# 3_classyTKL_EC_mcu.net
KiCad netlist of a schematic drawn in Altium Designer
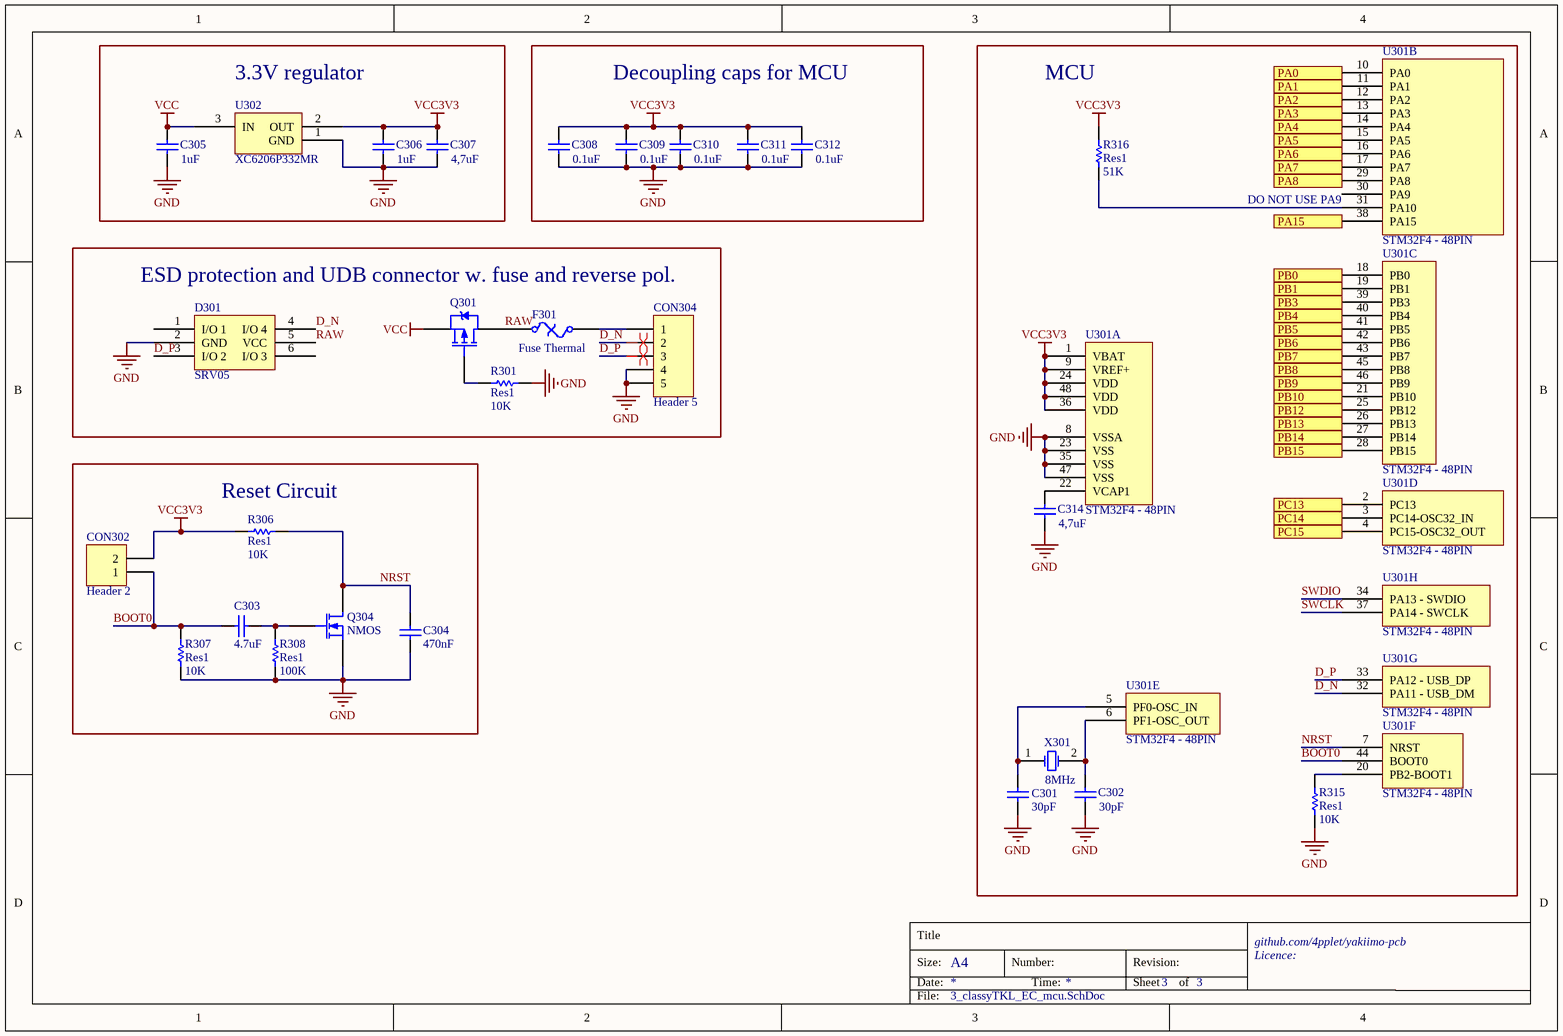
[diagram p0: 3_classyTKL_EC_mcu.SchDoc]

(export (version "E")
  (design (tool "Eeschema 10.0.6"))
  (components
    (comp (ref "C301")
      (value "30pF")
      (footprint "C0603[1608]")
      (description "Capacitor")
      (fields (field (name "LCSC PART #") "C22397") (field (name "MRF.PART") "CL10C300JB8NNNC"))
      (libsource (lib "Miscellaneous Devices") (part "Cap"))
    )
    (comp (ref "C302")
      (value "30pF")
      (footprint "C0603[1608]")
      (description "Capacitor")
      (fields (field (name "LCSC PART #") "C22397") (field (name "MRF.PART") "CL10C300JB8NNNC"))
      (libsource (lib "Miscellaneous Devices") (part "Cap"))
    )
    (comp (ref "C303")
      (value "4.7uF")
      (footprint "C0603[1608]")
      (description "Capacitor")
      (fields (field (name "LCSC PART #") "C19666") (field (name "MRF.PART") "CL10A475KO8NNNC"))
      (libsource (lib "Miscellaneous Devices") (part "Cap"))
    )
    (comp (ref "C304")
      (value "470nF")
      (footprint "C0603[1608]")
      (description "Capacitor")
      (fields (field (name "LCSC PART #") "C14663") (field (name "MRF.PART") "CC0603KRX7R9BB104"))
      (libsource (lib "Miscellaneous Devices") (part "Cap"))
    )
    (comp (ref "C305")
      (value "1uF")
      (footprint "C0603[1608]")
      (description "Capacitor")
      (fields (field (name "LCSC PART #") "C15849") (field (name "MRF.PART") "CL10A105KB8NNNC"))
      (libsource (lib "Miscellaneous Devices") (part "Cap"))
    )
    (comp (ref "C306")
      (value "1uF")
      (footprint "C0603[1608]")
      (description "Capacitor")
      (fields (field (name "LCSC PART #") "C15849") (field (name "MRF.PART") "CL10A105KB8NNNC"))
      (libsource (lib "Miscellaneous Devices") (part "Cap"))
    )
    (comp (ref "C307")
      (value "4,7uF")
      (footprint "C0603[1608]")
      (description "Capacitor")
      (fields (field (name "LCSC PART #") "C19666") (field (name "MRF.PART") "CL10A475KO8NNNC"))
      (libsource (lib "Miscellaneous Devices") (part "Cap"))
    )
    (comp (ref "C308")
      (value "0.1uF")
      (footprint "C0603[1608]")
      (description "Capacitor")
      (fields (field (name "LCSC PART #") "C14663") (field (name "MRF.PART") "CC0603KRX7R9BB104"))
      (libsource (lib "Miscellaneous Devices") (part "Cap"))
    )
    (comp (ref "C309")
      (value "0.1uF")
      (footprint "C0603[1608]")
      (description "Capacitor")
      (fields (field (name "LCSC PART #") "C14663") (field (name "MRF.PART") "CC0603KRX7R9BB104"))
      (libsource (lib "Miscellaneous Devices") (part "Cap"))
    )
    (comp (ref "C310")
      (value "0.1uF")
      (footprint "C0603[1608]")
      (description "Capacitor")
      (fields (field (name "LCSC PART #") "C14663") (field (name "MRF.PART") "CC0603KRX7R9BB104"))
      (libsource (lib "Miscellaneous Devices") (part "Cap"))
    )
    (comp (ref "C311")
      (value "0.1uF")
      (footprint "C0603[1608]")
      (description "Capacitor")
      (fields (field (name "LCSC PART #") "C14663") (field (name "MRF.PART") "CC0603KRX7R9BB104"))
      (libsource (lib "Miscellaneous Devices") (part "Cap"))
    )
    (comp (ref "C312")
      (value "0.1uF")
      (footprint "C0603[1608]")
      (description "Capacitor")
      (fields (field (name "LCSC PART #") "C14663") (field (name "MRF.PART") "CC0603KRX7R9BB104"))
      (libsource (lib "Miscellaneous Devices") (part "Cap"))
    )
    (comp (ref "C314")
      (value "4,7uF")
      (footprint "C0603[1608]")
      (description "Capacitor")
      (fields (field (name "LCSC PART #") "C19666") (field (name "MRF.PART") "CL10A475KO8NNNC"))
      (libsource (lib "Miscellaneous Devices") (part "Cap"))
    )
    (comp (ref "CON302")
      (value "Header 2")
      (footprint "HDR1X2")
      (description "Header, 2-Pin")
      (libsource (lib "Miscellaneous Connectors") (part "Header 2"))
    )
    (comp (ref "CON304")
      (value "Header 5")
      (footprint "JST SM04B-SRSS-TB")
      (description "JST for USB daughter board")
      (fields (field (name "LCSC PART #") "C160404") (field (name "MRF.PART") "SM04B-SRSS-TB(LF)(SN)"))
      (libsource (lib "Miscellaneous Connectors") (part "Header 5"))
    )
    (comp (ref "D301")
      (value "SRV05")
      (footprint "SOT-23-6")
      (fields (field (name "LCSC PART #") "C85364") (field (name "MRF.PART") "SRV05-4-P-T7"))
      (libsource (lib "Keebs") (part "SRV05"))
    )
    (comp (ref "F301")
      (value "Fuse Thermal")
      (footprint "C1206[3216]")
      (description "Thermal Fuse")
      (fields (field (name "LCSC PART #") "C135338") (field (name "MRF.PART") "ASMD1206-050"))
      (libsource (lib "Miscellaneous Devices") (part "Fuse Thermal"))
    )
    (comp (ref "Q301")
      (value "PMOS-2")
      (footprint "SOT-23-3")
      (description "P-Channel Power MOSFET")
      (fields (field (name "LCSC PART #") "C10487") (field (name "MRF.PART") "SI2301CDS-T1-GE3"))
      (libsource (lib "Miscellaneous Devices") (part "PMOS-2"))
    )
    (comp (ref "Q304")
      (value "NMOS")
      (footprint "SOT-23-3")
      (description "N-Channel MOSFET")
      (fields (field (name "LCSC PART #") "C8545") (field (name "MRF.PART") "2N7002"))
      (libsource (lib "Miscellaneous Devices") (part "MOSFET-N"))
    )
    (comp (ref "R301")
      (value "Res1")
      (footprint "R0603[1608]")
      (description "Resistor")
      (fields
        (field (name "ALTIUM_VALUE") "10K")
        (field (name "LCSC PART #") "C25804")
        (field (name "MRF.PART") "0603WAF1002T5E")
      )
      (libsource (lib "Miscellaneous Devices") (part "Res1"))
    )
    (comp (ref "R306")
      (value "Res1")
      (footprint "R0603[1608]")
      (description "Resistor")
      (fields
        (field (name "ALTIUM_VALUE") "10K")
        (field (name "LCSC PART #") "C25804")
        (field (name "MRF.PART") "0603WAF1002T5E")
      )
      (libsource (lib "Miscellaneous Devices") (part "Res1"))
    )
    (comp (ref "R307")
      (value "Res1")
      (footprint "R0603[1608]")
      (description "Resistor")
      (fields
        (field (name "ALTIUM_VALUE") "10K")
        (field (name "LCSC PART #") "C25804")
        (field (name "MRF.PART") "0603WAF1002T5E")
      )
      (libsource (lib "Miscellaneous Devices") (part "Res1"))
    )
    (comp (ref "R308")
      (value "Res1")
      (footprint "R0603[1608]")
      (description "Resistor")
      (fields
        (field (name "ALTIUM_VALUE") "100K")
        (field (name "LCSC PART #") "C25803")
        (field (name "MRF.PART") "0603WAF1003T5E")
      )
      (libsource (lib "Miscellaneous Devices") (part "Res1"))
    )
    (comp (ref "R315")
      (value "Res1")
      (footprint "R0603[1608]")
      (description "Resistor")
      (fields
        (field (name "ALTIUM_VALUE") "10K")
        (field (name "LCSC PART #") "C25804")
        (field (name "MRF.PART") "0603WAF1002T5E")
      )
      (libsource (lib "Miscellaneous Devices") (part "Res1"))
    )
    (comp (ref "R316")
      (value "Res1")
      (footprint "R0603[1608]")
      (description "Resistor")
      (fields
        (field (name "ALTIUM_VALUE") "51K")
        (field (name "LCSC PART #") "C23196")
        (field (name "MRF.PART") "0603WAF5102T5E")
      )
      (libsource (lib "Miscellaneous Devices") (part "Res1"))
    )
    (comp (ref "U301")
      (value "STM32F4 - 48PIN")
      (footprint "STM32 - COMBO 7x7mm")
      (fields (field (name "LCSC PART #") "C60420") (field (name "MRF.PART") "STM32F411CEU6"))
      (libsource (lib "Keebs") (part "STM32F4 - 48PIN"))
    )
    (comp (ref "U302")
      (value "XC6206P332MR")
      (footprint "SOT-23-3")
      (fields (field (name "LCSC PART #") "C5446"))
      (libsource (lib "Keebs") (part "SOT23 LDO"))
    )
    (comp (ref "X301")
      (value "8MHz")
      (footprint "CTS 445-series crystal")
      (description "Crystal Oscillator")
      (fields (field (name "LCSC PART #") "C115962") (field (name "MRF.PART") "X50328MSB2GI"))
      (libsource (lib "Miscellaneous Devices") (part "XTAL"))
    )
  )
  (nets
    (net (code "1") (name "/BOOT0") (class "Default")
      (node (ref "C303") (pin "1") (pinfunction "1_1") (pintype "passive"))
      (node (ref "CON302") (pin "1") (pinfunction "1_1") (pintype "passive"))
      (node (ref "R307") (pin "1") (pinfunction "1_1") (pintype "passive"))
      (node (ref "U301") (pin "44") (pinfunction "BOOT0_44") (pintype "passive"))
    )
    (net (code "2") (name "/D_N") (class "Default")
      (node (ref "CON304") (pin "2") (pinfunction "2_2") (pintype "passive"))
      (node (ref "D301") (pin "4") (pinfunction "I/O_4_4") (pintype "passive"))
      (node (ref "U301") (pin "32") (pinfunction "PA11_-_USB_DM_32") (pintype "passive"))
    )
    (net (code "3") (name "/D_P") (class "Default")
      (node (ref "CON304") (pin "3") (pinfunction "3_3") (pintype "passive"))
      (node (ref "D301") (pin "3") (pinfunction "I/O_2_3") (pintype "passive"))
      (node (ref "U301") (pin "33") (pinfunction "PA12_-_USB_DP_33") (pintype "passive"))
    )
    (net (code "4") (name "/NRST") (class "Default")
      (node (ref "C304") (pin "1") (pinfunction "1_1") (pintype "passive"))
      (node (ref "Q304") (pin "3") (pinfunction "D_3") (pintype "passive"))
      (node (ref "R306") (pin "2") (pinfunction "2_2") (pintype "passive"))
      (node (ref "U301") (pin "7") (pinfunction "NRST_7") (pintype "passive"))
    )
    (net (code "5") (name "/PA0") (class "Default")
      (node (ref "U301") (pin "10") (pinfunction "PA0_10") (pintype "passive"))
    )
    (net (code "6") (name "/PA1") (class "Default")
      (node (ref "U301") (pin "11") (pinfunction "PA1_11") (pintype "passive"))
    )
    (net (code "7") (name "/PA2") (class "Default")
      (node (ref "U301") (pin "12") (pinfunction "PA2_12") (pintype "passive"))
    )
    (net (code "8") (name "/PA3") (class "Default")
      (node (ref "U301") (pin "13") (pinfunction "PA3_13") (pintype "passive"))
    )
    (net (code "9") (name "/PA4") (class "Default")
      (node (ref "U301") (pin "14") (pinfunction "PA4_14") (pintype "passive"))
    )
    (net (code "10") (name "/PA5") (class "Default")
      (node (ref "U301") (pin "15") (pinfunction "PA5_15") (pintype "passive"))
    )
    (net (code "11") (name "/PA6") (class "Default")
      (node (ref "U301") (pin "16") (pinfunction "PA6_16") (pintype "passive"))
    )
    (net (code "12") (name "/PA7") (class "Default")
      (node (ref "U301") (pin "17") (pinfunction "PA7_17") (pintype "passive"))
    )
    (net (code "13") (name "/PA8") (class "Default")
      (node (ref "U301") (pin "29") (pinfunction "PA8_29") (pintype "passive"))
    )
    (net (code "14") (name "/PA15") (class "Default")
      (node (ref "U301") (pin "38") (pinfunction "PA15_38") (pintype "passive"))
    )
    (net (code "15") (name "/PB0") (class "Default")
      (node (ref "U301") (pin "18") (pinfunction "PB0_18") (pintype "passive"))
    )
    (net (code "16") (name "/PB1") (class "Default")
      (node (ref "U301") (pin "19") (pinfunction "PB1_19") (pintype "passive"))
    )
    (net (code "17") (name "/PB3") (class "Default")
      (node (ref "U301") (pin "39") (pinfunction "PB3_39") (pintype "passive"))
    )
    (net (code "18") (name "/PB4") (class "Default")
      (node (ref "U301") (pin "40") (pinfunction "PB4_40") (pintype "passive"))
    )
    (net (code "19") (name "/PB5") (class "Default")
      (node (ref "U301") (pin "41") (pinfunction "PB5_41") (pintype "passive"))
    )
    (net (code "20") (name "/PB6") (class "Default")
      (node (ref "U301") (pin "42") (pinfunction "PB6_42") (pintype "passive"))
    )
    (net (code "21") (name "/PB7") (class "Default")
      (node (ref "U301") (pin "43") (pinfunction "PB7_43") (pintype "passive"))
    )
    (net (code "22") (name "/PB8") (class "Default")
      (node (ref "U301") (pin "45") (pinfunction "PB8_45") (pintype "passive"))
    )
    (net (code "23") (name "/PB9") (class "Default")
      (node (ref "U301") (pin "46") (pinfunction "PB9_46") (pintype "passive"))
    )
    (net (code "24") (name "/PB10") (class "Default")
      (node (ref "U301") (pin "21") (pinfunction "PB10_21") (pintype "passive"))
    )
    (net (code "25") (name "/PB12") (class "Default")
      (node (ref "U301") (pin "25") (pinfunction "PB12_25") (pintype "passive"))
    )
    (net (code "26") (name "/PB13") (class "Default")
      (node (ref "U301") (pin "26") (pinfunction "PB13_26") (pintype "passive"))
    )
    (net (code "27") (name "/PB14") (class "Default")
      (node (ref "U301") (pin "27") (pinfunction "PB14_27") (pintype "passive"))
    )
    (net (code "28") (name "/PB15") (class "Default")
      (node (ref "U301") (pin "28") (pinfunction "PB15_28") (pintype "passive"))
    )
    (net (code "29") (name "/PC13") (class "Default")
      (node (ref "U301") (pin "2") (pinfunction "PC13_2") (pintype "passive"))
    )
    (net (code "30") (name "/PC14") (class "Default")
      (node (ref "U301") (pin "3") (pinfunction "PC14-OSC32_IN_3") (pintype "passive"))
    )
    (net (code "31") (name "/PC15") (class "Default")
      (node (ref "U301") (pin "4") (pinfunction "PC15-OSC32_OUT_4") (pintype "passive"))
    )
    (net (code "32") (name "/RAW") (class "Default")
      (node (ref "D301") (pin "5") (pinfunction "VCC_5") (pintype "passive"))
      (node (ref "F301") (pin "1") (pinfunction "1_1") (pintype "passive"))
      (node (ref "Q301") (pin "3") (pinfunction "D_3") (pintype "passive"))
    )
    (net (code "33") (name "/SWCLK") (class "Default")
      (node (ref "U301") (pin "37") (pinfunction "PA14_-_SWCLK_37") (pintype "passive"))
    )
    (net (code "34") (name "/SWDIO") (class "Default")
      (node (ref "U301") (pin "34") (pinfunction "PA13_-_SWDIO_34") (pintype "passive"))
    )
    (net (code "35") (name "GND") (class "Default")
      (node (ref "C301") (pin "1") (pinfunction "1_1") (pintype "passive"))
      (node (ref "C302") (pin "1") (pinfunction "1_1") (pintype "passive"))
      (node (ref "C304") (pin "2") (pinfunction "2_2") (pintype "passive"))
      (node (ref "C305") (pin "1") (pinfunction "1_1") (pintype "passive"))
      (node (ref "C306") (pin "1") (pinfunction "1_1") (pintype "passive"))
      (node (ref "C307") (pin "1") (pinfunction "1_1") (pintype "passive"))
      (node (ref "C308") (pin "1") (pinfunction "1_1") (pintype "passive"))
      (node (ref "C309") (pin "1") (pinfunction "1_1") (pintype "passive"))
      (node (ref "C310") (pin "1") (pinfunction "1_1") (pintype "passive"))
      (node (ref "C311") (pin "1") (pinfunction "1_1") (pintype "passive"))
      (node (ref "C312") (pin "1") (pinfunction "1_1") (pintype "passive"))
      (node (ref "C314") (pin "1") (pinfunction "1_1") (pintype "passive"))
      (node (ref "CON304") (pin "4") (pinfunction "4_4") (pintype "passive"))
      (node (ref "CON304") (pin "5") (pinfunction "5_5") (pintype "passive"))
      (node (ref "D301") (pin "2") (pinfunction "GND_2") (pintype "passive"))
      (node (ref "Q304") (pin "2") (pinfunction "S_2") (pintype "passive"))
      (node (ref "R301") (pin "2") (pinfunction "2_2") (pintype "passive"))
      (node (ref "R307") (pin "2") (pinfunction "2_2") (pintype "passive"))
      (node (ref "R308") (pin "2") (pinfunction "2_2") (pintype "passive"))
      (node (ref "R315") (pin "2") (pinfunction "2_2") (pintype "passive"))
      (node (ref "U301") (pin "23") (pinfunction "VSS_23") (pintype "passive"))
      (node (ref "U301") (pin "35") (pinfunction "VSS_35") (pintype "passive"))
      (node (ref "U301") (pin "47") (pinfunction "VSS_47") (pintype "passive"))
      (node (ref "U301") (pin "8") (pinfunction "VSSA_8") (pintype "passive"))
      (node (ref "U302") (pin "1") (pinfunction "GND_1") (pintype "passive"))
    )
    (net (code "36") (name "Net-(CON304-Pad1)") (class "Default")
      (node (ref "CON304") (pin "1") (pinfunction "1_1") (pintype "passive"))
      (node (ref "F301") (pin "2") (pinfunction "2_2") (pintype "passive"))
    )
    (net (code "37") (name "Net-(Q301-G)") (class "Default")
      (node (ref "Q301") (pin "1") (pinfunction "G_1") (pintype "passive"))
      (node (ref "R301") (pin "1") (pinfunction "1_1") (pintype "passive"))
    )
    (net (code "38") (name "Net-(Q304-G)") (class "Default")
      (node (ref "C303") (pin "2") (pinfunction "2_2") (pintype "passive"))
      (node (ref "Q304") (pin "1") (pinfunction "G_1") (pintype "passive"))
      (node (ref "R308") (pin "1") (pinfunction "1_1") (pintype "passive"))
    )
    (net (code "39") (name "Net-(U301A-VCAP1)") (class "Default")
      (node (ref "C314") (pin "2") (pinfunction "2_2") (pintype "passive"))
      (node (ref "U301") (pin "22") (pinfunction "VCAP1_22") (pintype "passive"))
    )
    (net (code "40") (name "Net-(U301B-PA10)") (class "Default")
      (node (ref "R316") (pin "2") (pinfunction "2_2") (pintype "passive"))
      (node (ref "U301") (pin "31") (pinfunction "PA10_31") (pintype "passive"))
    )
    (net (code "41") (name "Net-(U301E-PF0-OSC_IN)") (class "Default")
      (node (ref "C301") (pin "2") (pinfunction "2_2") (pintype "passive"))
      (node (ref "U301") (pin "5") (pinfunction "PF0-OSC_IN_5") (pintype "passive"))
      (node (ref "X301") (pin "1") (pinfunction "OSC1_1") (pintype "passive"))
    )
    (net (code "42") (name "Net-(U301E-PF1-OSC_OUT)") (class "Default")
      (node (ref "C302") (pin "2") (pinfunction "2_2") (pintype "passive"))
      (node (ref "U301") (pin "6") (pinfunction "PF1-OSC_OUT_6") (pintype "passive"))
      (node (ref "X301") (pin "2") (pinfunction "OSC2_2") (pintype "passive"))
    )
    (net (code "43") (name "Net-(U301F-PB2-BOOT1)") (class "Default")
      (node (ref "R315") (pin "1") (pinfunction "1_1") (pintype "passive"))
      (node (ref "U301") (pin "20") (pinfunction "PB2-BOOT1_20") (pintype "passive"))
    )
    (net (code "44") (name "VCC") (class "Default")
      (node (ref "C305") (pin "2") (pinfunction "2_2") (pintype "passive"))
      (node (ref "Q301") (pin "2") (pinfunction "S_2") (pintype "passive"))
      (node (ref "U302") (pin "3") (pinfunction "IN_3") (pintype "passive"))
    )
    (net (code "45") (name "VCC3V3") (class "Default")
      (node (ref "C306") (pin "2") (pinfunction "2_2") (pintype "passive"))
      (node (ref "C307") (pin "2") (pinfunction "2_2") (pintype "passive"))
      (node (ref "C308") (pin "2") (pinfunction "2_2") (pintype "passive"))
      (node (ref "C309") (pin "2") (pinfunction "2_2") (pintype "passive"))
      (node (ref "C310") (pin "2") (pinfunction "2_2") (pintype "passive"))
      (node (ref "C311") (pin "2") (pinfunction "2_2") (pintype "passive"))
      (node (ref "C312") (pin "2") (pinfunction "2_2") (pintype "passive"))
      (node (ref "CON302") (pin "2") (pinfunction "2_2") (pintype "passive"))
      (node (ref "R306") (pin "1") (pinfunction "1_1") (pintype "passive"))
      (node (ref "R316") (pin "1") (pinfunction "1_1") (pintype "passive"))
      (node (ref "U301") (pin "1") (pinfunction "VBAT_1") (pintype "passive"))
      (node (ref "U301") (pin "24") (pinfunction "VDD_24") (pintype "passive"))
      (node (ref "U301") (pin "36") (pinfunction "VDD_36") (pintype "passive"))
      (node (ref "U301") (pin "48") (pinfunction "VDD_48") (pintype "passive"))
      (node (ref "U301") (pin "9") (pinfunction "VREF+_9") (pintype "passive"))
      (node (ref "U302") (pin "2") (pinfunction "OUT_2") (pintype "passive"))
    )
    (net (code "46") (name "unconnected-(D301-I{slash}O_1-Pad1)") (class "Default")
      (node (ref "D301") (pin "1") (pinfunction "I/O_1_1") (pintype "passive"))
    )
    (net (code "47") (name "unconnected-(D301-I{slash}O_3-Pad6)") (class "Default")
      (node (ref "D301") (pin "6") (pinfunction "I/O_3_6") (pintype "passive"))
    )
    (net (code "48") (name "unconnected-(U301B-PA9-Pad30)") (class "Default")
      (node (ref "U301") (pin "30") (pinfunction "PA9_30") (pintype "passive"))
    )
  )
)
